# 7duino.net
KiCad netlist of a schematic drawn in EAGLE
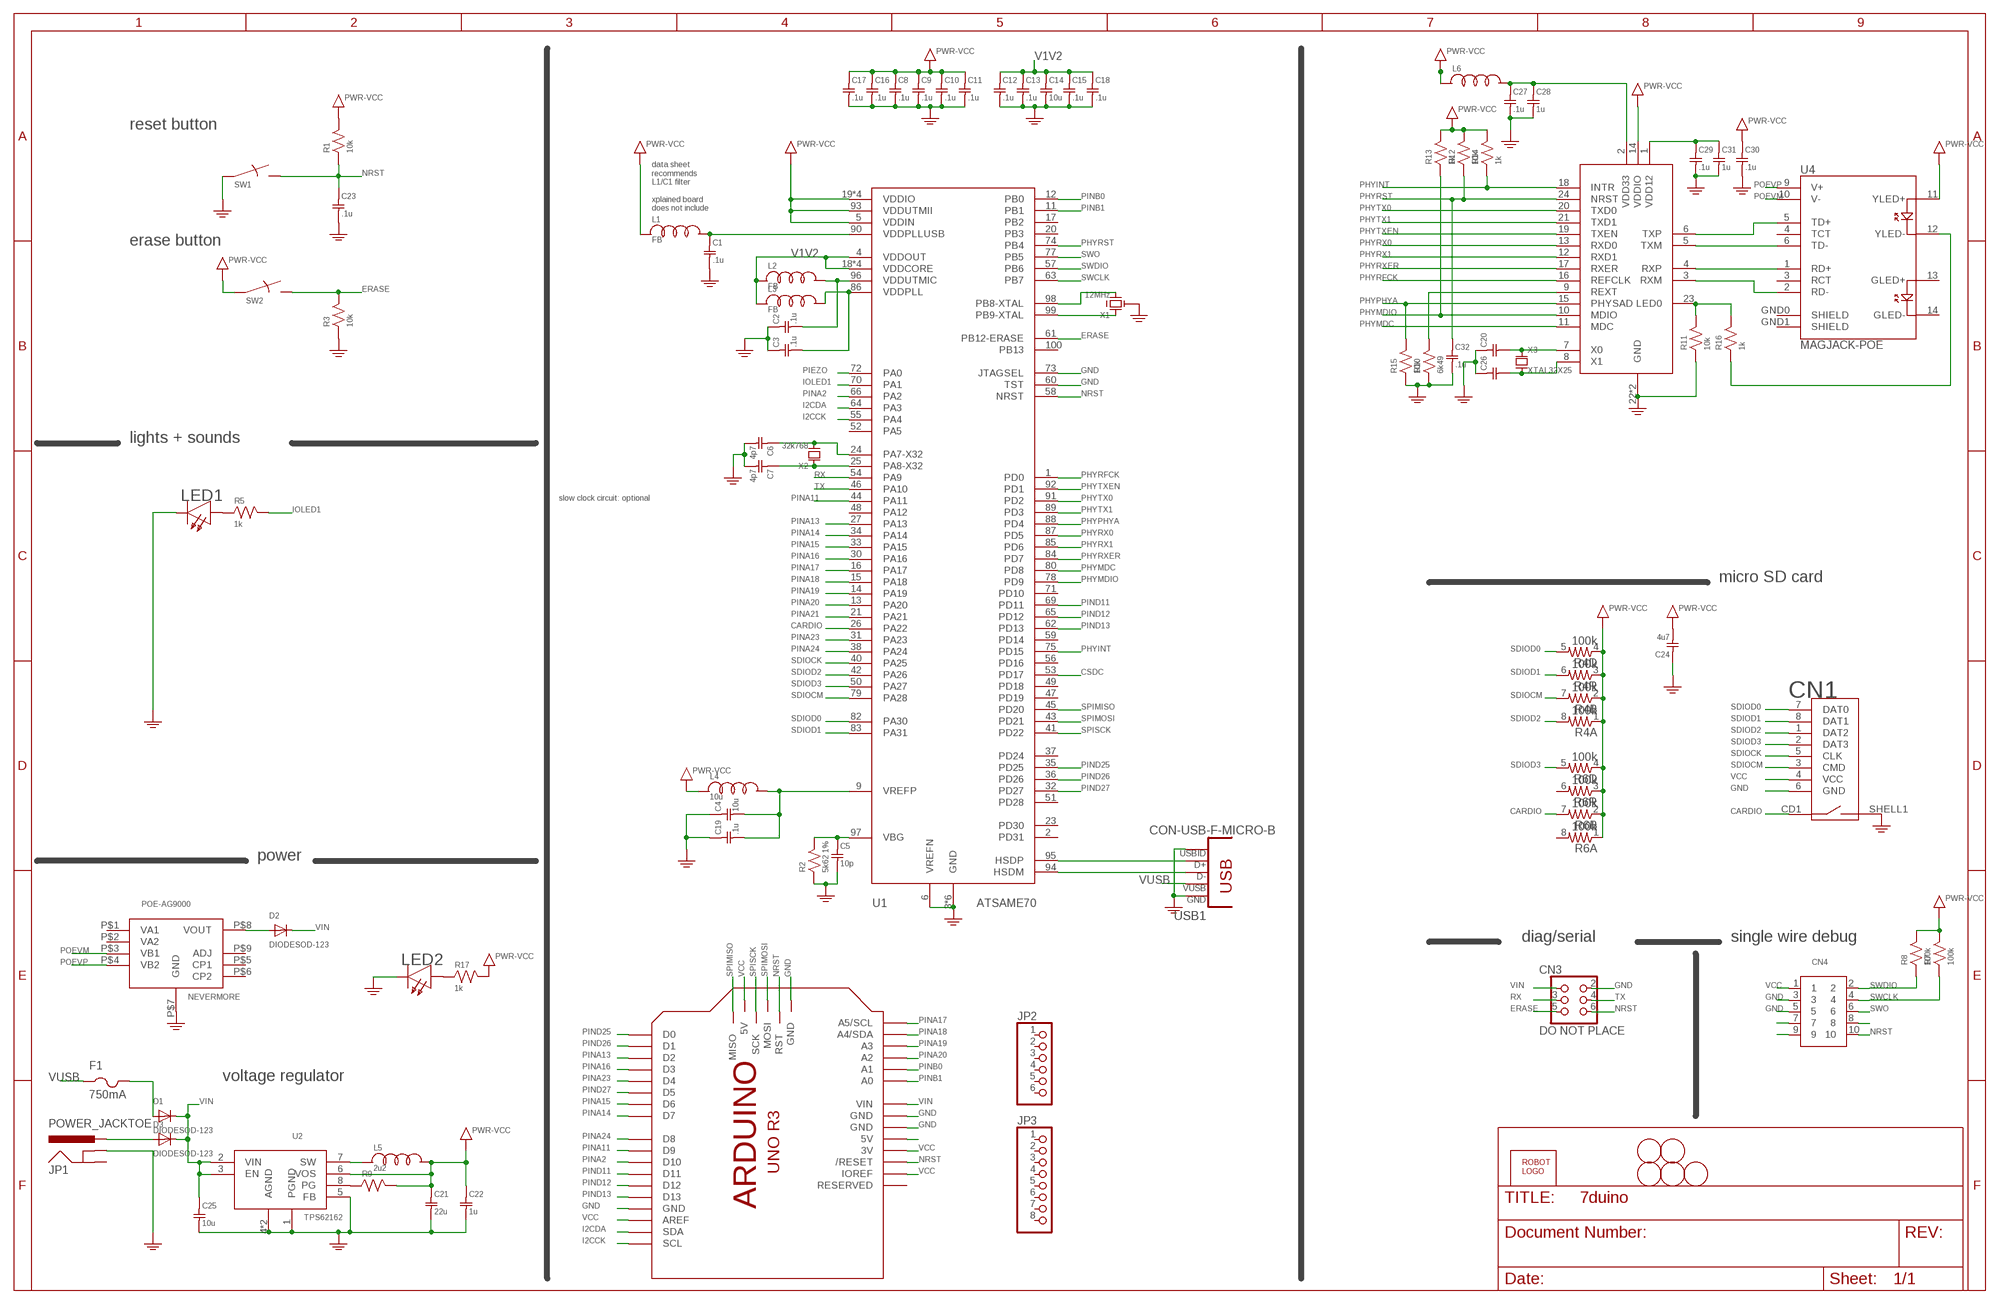
[diagram p0: schematic, sheet 1]

(export (version "E")
  (design (tool "Eeschema 10.0.6"))
  (components
    (comp (ref "C1")
      (value ".1u")
      (footprint "eagle-import:SMD0402")
      (libsource (lib "eagle-import") (part "C-0402"))
    )
    (comp (ref "C2")
      (value ".1u")
      (footprint "eagle-import:SMD0402")
      (libsource (lib "eagle-import") (part "C-0402"))
    )
    (comp (ref "C3")
      (value ".1u")
      (footprint "eagle-import:SMD0402")
      (libsource (lib "eagle-import") (part "C-0402"))
    )
    (comp (ref "C4")
      (value "10u")
      (footprint "eagle-import:SMD0603")
      (libsource (lib "eagle-import") (part "C0603"))
    )
    (comp (ref "C5")
      (value "10p")
      (footprint "eagle-import:SMD0402")
      (libsource (lib "eagle-import") (part "C-0402"))
    )
    (comp (ref "C6")
      (value "4p7")
      (footprint "eagle-import:SMD0402")
      (libsource (lib "eagle-import") (part "C-0402"))
    )
    (comp (ref "C7")
      (value "4p7")
      (footprint "eagle-import:SMD0402")
      (libsource (lib "eagle-import") (part "C-0402"))
    )
    (comp (ref "C8")
      (value ".1u")
      (footprint "eagle-import:SMD0402")
      (libsource (lib "eagle-import") (part "C-0402"))
    )
    (comp (ref "C9")
      (value ".1u")
      (footprint "eagle-import:SMD0402")
      (libsource (lib "eagle-import") (part "C-0402"))
    )
    (comp (ref "C10")
      (value ".1u")
      (footprint "eagle-import:SMD0402")
      (libsource (lib "eagle-import") (part "C-0402"))
    )
    (comp (ref "C11")
      (value ".1u")
      (footprint "eagle-import:SMD0402")
      (libsource (lib "eagle-import") (part "C-0402"))
    )
    (comp (ref "C12")
      (value ".1u")
      (footprint "eagle-import:SMD0402")
      (libsource (lib "eagle-import") (part "C-0402"))
    )
    (comp (ref "C13")
      (value ".1u")
      (footprint "eagle-import:SMD0402")
      (libsource (lib "eagle-import") (part "C-0402"))
    )
    (comp (ref "C14")
      (value "10u")
      (footprint "eagle-import:SMD0603")
      (libsource (lib "eagle-import") (part "C0603"))
    )
    (comp (ref "C15")
      (value ".1u")
      (footprint "eagle-import:SMD0402")
      (libsource (lib "eagle-import") (part "C-0402"))
    )
    (comp (ref "C16")
      (value ".1u")
      (footprint "eagle-import:SMD0402")
      (libsource (lib "eagle-import") (part "C-0402"))
    )
    (comp (ref "C17")
      (value ".1u")
      (footprint "eagle-import:SMD0402")
      (libsource (lib "eagle-import") (part "C-0402"))
    )
    (comp (ref "C18")
      (value ".1u")
      (footprint "eagle-import:SMD0402")
      (libsource (lib "eagle-import") (part "C-0402"))
    )
    (comp (ref "C19")
      (value ".1u")
      (footprint "eagle-import:SMD0402")
      (libsource (lib "eagle-import") (part "C-0402"))
    )
    (comp (ref "C20")
      (value "C-0402")
      (footprint "eagle-import:SMD0402")
      (libsource (lib "eagle-import") (part "C-0402"))
    )
    (comp (ref "C21")
      (value "22u")
      (footprint "eagle-import:SMD0805")
      (libsource (lib "eagle-import") (part "C0805"))
    )
    (comp (ref "C22")
      (value "1u")
      (footprint "eagle-import:SMD0402")
      (libsource (lib "eagle-import") (part "C-0402"))
    )
    (comp (ref "C23")
      (value ".1u")
      (footprint "eagle-import:SMD0402")
      (libsource (lib "eagle-import") (part "C-0402"))
    )
    (comp (ref "C24")
      (value "4u7")
      (footprint "eagle-import:SMD0603")
      (libsource (lib "eagle-import") (part "C0603"))
    )
    (comp (ref "C25")
      (value "10u")
      (footprint "eagle-import:SMD0603")
      (libsource (lib "eagle-import") (part "C0603"))
    )
    (comp (ref "C26")
      (value "C-0402")
      (footprint "eagle-import:SMD0402")
      (libsource (lib "eagle-import") (part "C-0402"))
    )
    (comp (ref "C27")
      (value ".1u")
      (footprint "eagle-import:SMD0402")
      (libsource (lib "eagle-import") (part "C-0402"))
    )
    (comp (ref "C28")
      (value "1u")
      (footprint "eagle-import:SMD0402")
      (libsource (lib "eagle-import") (part "C-0402"))
    )
    (comp (ref "C29")
      (value ".1u")
      (footprint "eagle-import:SMD0402")
      (libsource (lib "eagle-import") (part "C-0402"))
    )
    (comp (ref "C30")
      (value ".1u")
      (footprint "eagle-import:SMD0402")
      (libsource (lib "eagle-import") (part "C-0402"))
    )
    (comp (ref "C31")
      (value "1u")
      (footprint "eagle-import:SMD0402")
      (libsource (lib "eagle-import") (part "C-0402"))
    )
    (comp (ref "C32")
      (value ".1u")
      (footprint "eagle-import:SMD0402")
      (libsource (lib "eagle-import") (part "C-0402"))
    )
    (comp (ref "CN1")
      (value "MICROSD-EJECT")
      (footprint "eagle-import:MICROSD_EJECTOR")
      (libsource (lib "eagle-import") (part "MICROSD-EJECT"))
    )
    (comp (ref "CN3")
      (value "DO NOT PLACE")
      (footprint "eagle-import:HEADER-3X2-POGO")
      (libsource (lib "eagle-import") (part "HEADER-3X2-POGO"))
    )
    (comp (ref "CN4")
      (value "DO NOT PLACE")
      (footprint "eagle-import:M127-5X2-F")
      (libsource (lib "eagle-import") (part "HEADER-5X2-SMD-F"))
    )
    (comp (ref "D1")
      (value "DIODESOD-123")
      (footprint "eagle-import:SOD-123")
      (libsource (lib "eagle-import") (part "DIODESOD-123"))
    )
    (comp (ref "D2")
      (value "DIODESOD-123")
      (footprint "eagle-import:SOD-123")
      (libsource (lib "eagle-import") (part "DIODESOD-123"))
    )
    (comp (ref "D3")
      (value "DIODESOD-123")
      (footprint "eagle-import:SOD-123")
      (libsource (lib "eagle-import") (part "DIODESOD-123"))
    )
    (comp (ref "F1")
      (value "750mA")
      (footprint "eagle-import:SMD1206")
      (libsource (lib "eagle-import") (part "FUSE"))
    )
    (comp (ref "JP1")
      (value "POWER_JACKTOE")
      (footprint "eagle-import:POWER_JACK_SMD_OVERPASTE_TOE")
      (libsource (lib "eagle-import") (part "POWER_JACKTOE"))
    )
    (comp (ref "JP2")
      (value "PINHD-1X6CLEAN")
      (footprint "eagle-import:1X06-CLEAN")
      (libsource (lib "eagle-import") (part "PINHD-1X6CLEAN"))
    )
    (comp (ref "JP3")
      (value "PINHD-1X8CLEANBIG")
      (footprint "eagle-import:1X08-CLEANBIG")
      (libsource (lib "eagle-import") (part "PINHD-1X8CLEANBIG"))
    )
    (comp (ref "L1")
      (value "FB")
      (footprint "eagle-import:SMD0402")
      (libsource (lib "eagle-import") (part "L-0402"))
    )
    (comp (ref "L2")
      (value "FB")
      (footprint "eagle-import:SMD0402")
      (libsource (lib "eagle-import") (part "L-0402"))
    )
    (comp (ref "L3")
      (value "FB")
      (footprint "eagle-import:SMD0402")
      (libsource (lib "eagle-import") (part "L-0402"))
    )
    (comp (ref "L4")
      (value "10u")
      (footprint "eagle-import:SMD0402")
      (libsource (lib "eagle-import") (part "L-0402"))
    )
    (comp (ref "L5")
      (value "2u2")
      (footprint "eagle-import:SMD1210")
      (libsource (lib "eagle-import") (part "L-1210"))
    )
    (comp (ref "L6")
      (value "L-0402")
      (footprint "eagle-import:SMD0402")
      (libsource (lib "eagle-import") (part "L-0402"))
    )
    (comp (ref "LED1")
      (value "white")
      (footprint "eagle-import:SMD0603D")
      (libsource (lib "eagle-import") (part "LED"))
    )
    (comp (ref "LED2")
      (value "white")
      (footprint "eagle-import:SMD0603D")
      (libsource (lib "eagle-import") (part "LED"))
    )
    (comp (ref "M1")
      (value "ARDUINO_R3_ICSP_NODIM")
      (footprint "eagle-import:ARDUINOR3_ICSP_NODIM")
      (libsource (lib "eagle-import") (part "ARDUINO_R3_ICSP_NODIM"))
    )
    (comp (ref "NEVERMORE")
      (value "POE-AG9000")
      (footprint "eagle-import:POE-AG9000")
      (libsource (lib "eagle-import") (part "POE-AG9000"))
    )
    (comp (ref "R1")
      (value "10k")
      (footprint "eagle-import:SMD0402")
      (libsource (lib "eagle-import") (part "R-0402"))
    )
    (comp (ref "R2")
      (value "5k62 1%")
      (footprint "eagle-import:SMD0402")
      (libsource (lib "eagle-import") (part "R-0402"))
    )
    (comp (ref "R3")
      (value "10k")
      (footprint "eagle-import:SMD0402")
      (libsource (lib "eagle-import") (part "R-0402"))
    )
    (comp (ref "R4")
      (value "100k")
      (footprint "eagle-import:SMD-0603-ARV")
      (libsource (lib "eagle-import") (part "R-ARRAY40603-ARV"))
    )
    (comp (ref "R5")
      (value "1k")
      (footprint "eagle-import:SMD0402")
      (libsource (lib "eagle-import") (part "R-0402"))
    )
    (comp (ref "R6")
      (value "100k")
      (footprint "eagle-import:SMD-0603-ARV")
      (libsource (lib "eagle-import") (part "R-ARRAY40603-ARV"))
    )
    (comp (ref "R7")
      (value "100k")
      (footprint "eagle-import:SMD0402")
      (libsource (lib "eagle-import") (part "R-0402"))
    )
    (comp (ref "R8")
      (value "100k")
      (footprint "eagle-import:SMD0402")
      (libsource (lib "eagle-import") (part "R-0402"))
    )
    (comp (ref "R9")
      (value "R-0402")
      (footprint "eagle-import:SMD0402")
      (libsource (lib "eagle-import") (part "R-0402"))
    )
    (comp (ref "R10")
      (value "6k49")
      (footprint "eagle-import:SMD0402")
      (libsource (lib "eagle-import") (part "R-0402"))
    )
    (comp (ref "R11")
      (value "10k")
      (footprint "eagle-import:SMD0402")
      (libsource (lib "eagle-import") (part "R-0402"))
    )
    (comp (ref "R12")
      (value "10k")
      (footprint "eagle-import:SMD0402")
      (libsource (lib "eagle-import") (part "R-0402"))
    )
    (comp (ref "R13")
      (value "1k")
      (footprint "eagle-import:SMD0402")
      (libsource (lib "eagle-import") (part "R-0402"))
    )
    (comp (ref "R14")
      (value "1k")
      (footprint "eagle-import:SMD0402")
      (libsource (lib "eagle-import") (part "R-0402"))
    )
    (comp (ref "R15")
      (value "10k")
      (footprint "eagle-import:SMD0402")
      (libsource (lib "eagle-import") (part "R-0402"))
    )
    (comp (ref "R16")
      (value "1k")
      (footprint "eagle-import:SMD0402")
      (libsource (lib "eagle-import") (part "R-0402"))
    )
    (comp (ref "R17")
      (value "1k")
      (footprint "eagle-import:SMD0402")
      (libsource (lib "eagle-import") (part "R-0402"))
    )
    (comp (ref "SW1")
      (value "SWITCHKMR211")
      (footprint "eagle-import:KMR211")
      (libsource (lib "eagle-import") (part "SWITCHKMR211"))
    )
    (comp (ref "SW2")
      (value "SWITCHKMR211")
      (footprint "eagle-import:KMR211")
      (libsource (lib "eagle-import") (part "SWITCHKMR211"))
    )
    (comp (ref "U$1")
      (value "ROBOTMAN-LOGO2")
      (footprint "eagle-import:ROBOTMAN-LOGO2")
      (libsource (lib "eagle-import") (part "ROBOTMAN-LOGO2"))
    )
    (comp (ref "U$2")
      (value "FIDUCIAL")
      (footprint "eagle-import:FIDUCIAL_1MM")
      (libsource (lib "eagle-import") (part "FIDUCIAL"))
    )
    (comp (ref "U$3")
      (value "FIDUCIAL")
      (footprint "eagle-import:FIDUCIAL_1MM")
      (libsource (lib "eagle-import") (part "FIDUCIAL"))
    )
    (comp (ref "U$4")
      (value "FIDUCIAL")
      (footprint "eagle-import:FIDUCIAL_1MM")
      (libsource (lib "eagle-import") (part "FIDUCIAL"))
    )
    (comp (ref "U$5")
      (value "FIDUCIAL")
      (footprint "eagle-import:FIDUCIAL_1MM")
      (libsource (lib "eagle-import") (part "FIDUCIAL"))
    )
    (comp (ref "U$6")
      (value "FIDUCIAL")
      (footprint "eagle-import:FIDUCIAL_1MM")
      (libsource (lib "eagle-import") (part "FIDUCIAL"))
    )
    (comp (ref "U1")
      (value "ATSAME70")
      (footprint "eagle-import:TQFP-100-14X14MM")
      (libsource (lib "eagle-import") (part "ATSAME70"))
    )
    (comp (ref "U2")
      (value "TPS62162")
      (footprint "eagle-import:WSON8")
      (libsource (lib "eagle-import") (part "TPS62125"))
    )
    (comp (ref "U3")
      (value "KSZ8081RNA")
      (footprint "eagle-import:LGA24EP")
      (libsource (lib "eagle-import") (part "KSZ8081RNA"))
    )
    (comp (ref "U4")
      (value "MAGJACK-POE")
      (footprint "eagle-import:MAGJACK-POE")
      (libsource (lib "eagle-import") (part "MAGJACK-POE"))
    )
    (comp (ref "USB1")
      (value "CON-USB-F-MICRO-B")
      (footprint "eagle-import:CONN_USB_MICRO-B")
      (libsource (lib "eagle-import") (part "CON-USB-F-MICRO-B"))
    )
    (comp (ref "X1")
      (value "12MHz")
      (footprint "eagle-import:RESONATOR-CSTCE")
      (libsource (lib "eagle-import") (part "RESONATORCTCE"))
    )
    (comp (ref "X2")
      (value "32k768")
      (footprint "eagle-import:XTAL-32X15")
      (libsource (lib "eagle-import") (part "XTAL32X15"))
    )
    (comp (ref "X3")
      (value "XTAL32X25")
      (footprint "eagle-import:XTAL-32X25")
      (libsource (lib "eagle-import") (part "XTAL32X25"))
    )
  )
  (nets
    (net (code "1") (name "/CARDIO") (class "Default")
      (node (ref "CN1") (pin "CD1") (pinfunction "SW1_CD1") (pintype "bidirectional"))
      (node (ref "R6") (pin "7") (pinfunction "2_7") (pintype "passive"))
      (node (ref "U1") (pin "26") (pinfunction "PA22_26") (pintype "bidirectional"))
    )
    (net (code "2") (name "/CSDC") (class "Default")
      (node (ref "U1") (pin "53") (pinfunction "PD17_53") (pintype "bidirectional"))
    )
    (net (code "3") (name "/ERASE") (class "Default")
      (node (ref "CN3") (pin "5") (pinfunction "P$5_5") (pintype "passive"))
      (node (ref "R3") (pin "2") (pinfunction "P$2_2") (pintype "passive"))
      (node (ref "SW2") (pin "2") (pinfunction "P$2_2") (pintype "passive"))
      (node (ref "SW2") (pin "4") (pinfunction "P$2_4") (pintype "passive"))
      (node (ref "U1") (pin "61") (pinfunction "PB12-ERASE_61") (pintype "bidirectional"))
    )
    (net (code "4") (name "/I2CCK") (class "Default")
      (node (ref "M1") (pin "SCL") (pinfunction "SCL_SCL") (pintype "bidirectional"))
      (node (ref "U1") (pin "55") (pinfunction "PA4_55") (pintype "bidirectional"))
    )
    (net (code "5") (name "/I2CDA") (class "Default")
      (node (ref "M1") (pin "SDA") (pinfunction "SDA_SDA") (pintype "bidirectional"))
      (node (ref "U1") (pin "64") (pinfunction "PA3_64") (pintype "bidirectional"))
    )
    (net (code "6") (name "/IOLED1") (class "Default")
      (node (ref "R5") (pin "2") (pinfunction "P$2_2") (pintype "passive"))
      (node (ref "U1") (pin "70") (pinfunction "PA1_70") (pintype "bidirectional"))
    )
    (net (code "7") (name "/NRST") (class "Default")
      (node (ref "C23") (pin "1") (pinfunction "P$1_1") (pintype "passive"))
      (node (ref "CN3") (pin "6") (pinfunction "P$6_6") (pintype "passive"))
      (node (ref "CN4") (pin "10") (pinfunction "10_10") (pintype "passive"))
      (node (ref "M1") (pin "RESET") (pinfunction "/RESET_RESET") (pintype "bidirectional"))
      (node (ref "M1") (pin "RESET_ICSP") (pinfunction "RST_RESET_ICSP") (pintype "passive"))
      (node (ref "R1") (pin "1") (pinfunction "P$1_1") (pintype "passive"))
      (node (ref "SW1") (pin "2") (pinfunction "P$2_2") (pintype "passive"))
      (node (ref "SW1") (pin "4") (pinfunction "P$2_4") (pintype "passive"))
      (node (ref "U1") (pin "58") (pinfunction "NRST_58") (pintype "bidirectional"))
    )
    (net (code "8") (name "/PHYINT") (class "Default")
      (node (ref "R14") (pin "1") (pinfunction "P$1_1") (pintype "passive"))
      (node (ref "U1") (pin "75") (pinfunction "PD15_75") (pintype "bidirectional"))
      (node (ref "U3") (pin "18") (pinfunction "INTR_18") (pintype "bidirectional"))
    )
    (net (code "9") (name "/PHYMDC") (class "Default")
      (node (ref "U1") (pin "80") (pinfunction "PD8_80") (pintype "bidirectional"))
      (node (ref "U3") (pin "11") (pinfunction "MDC_11") (pintype "bidirectional"))
    )
    (net (code "10") (name "/PHYMDIO") (class "Default")
      (node (ref "R13") (pin "1") (pinfunction "P$1_1") (pintype "passive"))
      (node (ref "U1") (pin "78") (pinfunction "PD9_78") (pintype "bidirectional"))
      (node (ref "U3") (pin "10") (pinfunction "MDIO_10") (pintype "bidirectional"))
    )
    (net (code "11") (name "/PHYPHYA") (class "Default")
      (node (ref "R15") (pin "2") (pinfunction "P$2_2") (pintype "passive"))
      (node (ref "U1") (pin "88") (pinfunction "PD4_88") (pintype "bidirectional"))
      (node (ref "U3") (pin "15") (pinfunction "PHYSAD_15") (pintype "bidirectional"))
    )
    (net (code "12") (name "/PHYRFCK") (class "Default")
      (node (ref "U1") (pin "1") (pinfunction "PD0_1") (pintype "bidirectional"))
      (node (ref "U3") (pin "16") (pinfunction "REFCLK_16") (pintype "bidirectional"))
    )
    (net (code "13") (name "/PHYRST") (class "Default")
      (node (ref "C32") (pin "1") (pinfunction "P$1_1") (pintype "passive"))
      (node (ref "R12") (pin "1") (pinfunction "P$1_1") (pintype "passive"))
      (node (ref "U1") (pin "74") (pinfunction "PB4_74") (pintype "bidirectional"))
      (node (ref "U3") (pin "24") (pinfunction "NRST_24") (pintype "bidirectional"))
    )
    (net (code "14") (name "/PHYRX0") (class "Default")
      (node (ref "U1") (pin "87") (pinfunction "PD5_87") (pintype "bidirectional"))
      (node (ref "U3") (pin "13") (pinfunction "RXD0_13") (pintype "bidirectional"))
    )
    (net (code "15") (name "/PHYRX1") (class "Default")
      (node (ref "U1") (pin "85") (pinfunction "PD6_85") (pintype "bidirectional"))
      (node (ref "U3") (pin "12") (pinfunction "RXD1_12") (pintype "bidirectional"))
    )
    (net (code "16") (name "/PHYRXER") (class "Default")
      (node (ref "U1") (pin "84") (pinfunction "PD7_84") (pintype "bidirectional"))
      (node (ref "U3") (pin "17") (pinfunction "RXER_17") (pintype "bidirectional"))
    )
    (net (code "17") (name "/PHYTX0") (class "Default")
      (node (ref "U1") (pin "91") (pinfunction "PD2_91") (pintype "bidirectional"))
      (node (ref "U3") (pin "20") (pinfunction "TXD0_20") (pintype "bidirectional"))
    )
    (net (code "18") (name "/PHYTX1") (class "Default")
      (node (ref "U1") (pin "89") (pinfunction "PD3_89") (pintype "bidirectional"))
      (node (ref "U3") (pin "21") (pinfunction "TXD1_21") (pintype "bidirectional"))
    )
    (net (code "19") (name "/PHYTXEN") (class "Default")
      (node (ref "U1") (pin "92") (pinfunction "PD1_92") (pintype "bidirectional"))
      (node (ref "U3") (pin "19") (pinfunction "TXEN_19") (pintype "bidirectional"))
    )
    (net (code "20") (name "/PIEZO") (class "Default")
      (node (ref "U1") (pin "72") (pinfunction "PA0_72") (pintype "bidirectional"))
    )
    (net (code "21") (name "/PINA2") (class "Default")
      (node (ref "M1") (pin "D10") (pinfunction "D10_D10") (pintype "bidirectional"))
      (node (ref "U1") (pin "66") (pinfunction "PA2_66") (pintype "bidirectional"))
    )
    (net (code "22") (name "/PINA11") (class "Default")
      (node (ref "M1") (pin "D9") (pinfunction "D9_D9") (pintype "bidirectional"))
      (node (ref "U1") (pin "44") (pinfunction "PA11_44") (pintype "bidirectional"))
    )
    (net (code "23") (name "/PINA13") (class "Default")
      (node (ref "M1") (pin "D2") (pinfunction "D2_D2") (pintype "bidirectional"))
      (node (ref "U1") (pin "27") (pinfunction "PA13_27") (pintype "bidirectional"))
    )
    (net (code "24") (name "/PINA14") (class "Default")
      (node (ref "M1") (pin "D7") (pinfunction "D7_D7") (pintype "bidirectional"))
      (node (ref "U1") (pin "34") (pinfunction "PA14_34") (pintype "bidirectional"))
    )
    (net (code "25") (name "/PINA15") (class "Default")
      (node (ref "M1") (pin "D6") (pinfunction "D6_D6") (pintype "bidirectional"))
      (node (ref "U1") (pin "33") (pinfunction "PA15_33") (pintype "bidirectional"))
    )
    (net (code "26") (name "/PINA16") (class "Default")
      (node (ref "M1") (pin "D3") (pinfunction "D3_D3") (pintype "bidirectional"))
      (node (ref "U1") (pin "30") (pinfunction "PA16_30") (pintype "bidirectional"))
    )
    (net (code "27") (name "/PINA17") (class "Default")
      (node (ref "M1") (pin "A5") (pinfunction "A5/SCL_A5") (pintype "bidirectional"))
      (node (ref "U1") (pin "16") (pinfunction "PA17_16") (pintype "bidirectional"))
    )
    (net (code "28") (name "/PINA18") (class "Default")
      (node (ref "M1") (pin "A4") (pinfunction "A4/SDA_A4") (pintype "bidirectional"))
      (node (ref "U1") (pin "15") (pinfunction "PA18_15") (pintype "bidirectional"))
    )
    (net (code "29") (name "/PINA19") (class "Default")
      (node (ref "M1") (pin "A3") (pinfunction "A3_A3") (pintype "bidirectional"))
      (node (ref "U1") (pin "14") (pinfunction "PA19_14") (pintype "bidirectional"))
    )
    (net (code "30") (name "/PINA20") (class "Default")
      (node (ref "M1") (pin "A2") (pinfunction "A2_A2") (pintype "bidirectional"))
      (node (ref "U1") (pin "13") (pinfunction "PA20_13") (pintype "bidirectional"))
    )
    (net (code "31") (name "/PINA21") (class "Default")
      (node (ref "U1") (pin "21") (pinfunction "PA21_21") (pintype "bidirectional"))
    )
    (net (code "32") (name "/PINA23") (class "Default")
      (node (ref "M1") (pin "D4") (pinfunction "D4_D4") (pintype "bidirectional"))
      (node (ref "U1") (pin "31") (pinfunction "PA23_31") (pintype "bidirectional"))
    )
    (net (code "33") (name "/PINA24") (class "Default")
      (node (ref "M1") (pin "D8") (pinfunction "D8_D8") (pintype "bidirectional"))
      (node (ref "U1") (pin "38") (pinfunction "PA24_38") (pintype "bidirectional"))
    )
    (net (code "34") (name "/PINB0") (class "Default")
      (node (ref "M1") (pin "A1") (pinfunction "A1_A1") (pintype "bidirectional"))
      (node (ref "U1") (pin "12") (pinfunction "PB0_12") (pintype "bidirectional"))
    )
    (net (code "35") (name "/PINB1") (class "Default")
      (node (ref "M1") (pin "A0") (pinfunction "A0_A0") (pintype "bidirectional"))
      (node (ref "U1") (pin "11") (pinfunction "PB1_11") (pintype "bidirectional"))
    )
    (net (code "36") (name "/PIND11") (class "Default")
      (node (ref "M1") (pin "D11") (pinfunction "D11_D11") (pintype "bidirectional"))
      (node (ref "U1") (pin "69") (pinfunction "PD11_69") (pintype "bidirectional"))
    )
    (net (code "37") (name "/PIND12") (class "Default")
      (node (ref "M1") (pin "D12") (pinfunction "D12_D12") (pintype "bidirectional"))
      (node (ref "U1") (pin "65") (pinfunction "PD12_65") (pintype "bidirectional"))
    )
    (net (code "38") (name "/PIND13") (class "Default")
      (node (ref "M1") (pin "D13") (pinfunction "D13_D13") (pintype "bidirectional"))
      (node (ref "U1") (pin "62") (pinfunction "PD13_62") (pintype "bidirectional"))
    )
    (net (code "39") (name "/PIND25") (class "Default")
      (node (ref "M1") (pin "D0") (pinfunction "D0_D0") (pintype "bidirectional"))
      (node (ref "U1") (pin "35") (pinfunction "PD25_35") (pintype "bidirectional"))
    )
    (net (code "40") (name "/PIND26") (class "Default")
      (node (ref "M1") (pin "D1") (pinfunction "D1_D1") (pintype "bidirectional"))
      (node (ref "U1") (pin "36") (pinfunction "PD26_36") (pintype "bidirectional"))
    )
    (net (code "41") (name "/PIND27") (class "Default")
      (node (ref "M1") (pin "D5") (pinfunction "D5_D5") (pintype "bidirectional"))
      (node (ref "U1") (pin "32") (pinfunction "PD27_32") (pintype "bidirectional"))
    )
    (net (code "42") (name "/POEVM") (class "Default")
      (node (ref "NEVERMORE") (pin "P$3") (pinfunction "VB1_P$3") (pintype "bidirectional"))
      (node (ref "U4") (pin "10") (pinfunction "V-_10") (pintype "bidirectional"))
    )
    (net (code "43") (name "/POEVP") (class "Default")
      (node (ref "NEVERMORE") (pin "P$4") (pinfunction "VB2_P$4") (pintype "bidirectional"))
      (node (ref "U4") (pin "9") (pinfunction "V+_9") (pintype "bidirectional"))
    )
    (net (code "44") (name "/RX") (class "Default")
      (node (ref "CN3") (pin "3") (pinfunction "P$3_3") (pintype "passive"))
      (node (ref "U1") (pin "54") (pinfunction "PA9_54") (pintype "bidirectional"))
    )
    (net (code "45") (name "/SDIOCK") (class "Default")
      (node (ref "CN1") (pin "5") (pinfunction "CLK_5") (pintype "bidirectional"))
      (node (ref "U1") (pin "40") (pinfunction "PA25_40") (pintype "bidirectional"))
    )
    (net (code "46") (name "/SDIOCM") (class "Default")
      (node (ref "CN1") (pin "3") (pinfunction "CMD_3") (pintype "bidirectional"))
      (node (ref "R4") (pin "7") (pinfunction "2_7") (pintype "passive"))
      (node (ref "U1") (pin "79") (pinfunction "PA28_79") (pintype "bidirectional"))
    )
    (net (code "47") (name "/SDIOD0") (class "Default")
      (node (ref "CN1") (pin "7") (pinfunction "DAT0_7") (pintype "bidirectional"))
      (node (ref "R4") (pin "5") (pinfunction "2_5") (pintype "passive"))
      (node (ref "U1") (pin "82") (pinfunction "PA30_82") (pintype "bidirectional"))
    )
    (net (code "48") (name "/SDIOD1") (class "Default")
      (node (ref "CN1") (pin "8") (pinfunction "DAT1_8") (pintype "bidirectional"))
      (node (ref "R4") (pin "6") (pinfunction "2_6") (pintype "passive"))
      (node (ref "U1") (pin "83") (pinfunction "PA31_83") (pintype "bidirectional"))
    )
    (net (code "49") (name "/SDIOD2") (class "Default")
      (node (ref "CN1") (pin "1") (pinfunction "DAT2_1") (pintype "bidirectional"))
      (node (ref "R4") (pin "8") (pinfunction "2_8") (pintype "passive"))
      (node (ref "U1") (pin "42") (pinfunction "PA26_42") (pintype "bidirectional"))
    )
    (net (code "50") (name "/SDIOD3") (class "Default")
      (node (ref "CN1") (pin "2") (pinfunction "DAT3_2") (pintype "bidirectional"))
      (node (ref "R6") (pin "5") (pinfunction "2_5") (pintype "passive"))
      (node (ref "U1") (pin "50") (pinfunction "PA27_50") (pintype "bidirectional"))
    )
    (net (code "51") (name "/SPIMISO") (class "Default")
      (node (ref "M1") (pin "MISO") (pinfunction "MISO_MISO") (pintype "passive"))
      (node (ref "U1") (pin "45") (pinfunction "PD20_45") (pintype "bidirectional"))
    )
    (net (code "52") (name "/SPIMOSI") (class "Default")
      (node (ref "M1") (pin "MOSI") (pinfunction "MOSI_MOSI") (pintype "passive"))
      (node (ref "U1") (pin "43") (pinfunction "PD21_43") (pintype "bidirectional"))
    )
    (net (code "53") (name "/SPISCK") (class "Default")
      (node (ref "M1") (pin "SCK") (pinfunction "SCK_SCK") (pintype "passive"))
      (node (ref "U1") (pin "41") (pinfunction "PD22_41") (pintype "bidirectional"))
    )
    (net (code "54") (name "/SWCLK") (class "Default")
      (node (ref "CN4") (pin "4") (pinfunction "4_4") (pintype "passive"))
      (node (ref "R7") (pin "1") (pinfunction "P$1_1") (pintype "passive"))
      (node (ref "U1") (pin "63") (pinfunction "PB7_63") (pintype "bidirectional"))
    )
    (net (code "55") (name "/SWDIO") (class "Default")
      (node (ref "CN4") (pin "2") (pinfunction "2_2") (pintype "passive"))
      (node (ref "R8") (pin "1") (pinfunction "P$1_1") (pintype "passive"))
      (node (ref "U1") (pin "57") (pinfunction "PB6_57") (pintype "bidirectional"))
    )
    (net (code "56") (name "/SWO") (class "Default")
      (node (ref "CN4") (pin "6") (pinfunction "6_6") (pintype "passive"))
      (node (ref "U1") (pin "77") (pinfunction "PB5_77") (pintype "bidirectional"))
    )
    (net (code "57") (name "/TX") (class "Default")
      (node (ref "CN3") (pin "4") (pinfunction "P$4_4") (pintype "passive"))
      (node (ref "U1") (pin "46") (pinfunction "PA10_46") (pintype "bidirectional"))
    )
    (net (code "58") (name "/V1V2") (class "Default")
      (node (ref "C12") (pin "1") (pinfunction "P$1_1") (pintype "passive"))
      (node (ref "C13") (pin "1") (pinfunction "P$1_1") (pintype "passive"))
      (node (ref "C14") (pin "1") (pinfunction "P$1_1") (pintype "passive"))
      (node (ref "C15") (pin "1") (pinfunction "P$1_1") (pintype "passive"))
      (node (ref "C18") (pin "1") (pinfunction "P$1_1") (pintype "passive"))
      (node (ref "L2") (pin "1") (pinfunction "P$1_1") (pintype "passive"))
      (node (ref "L3") (pin "1") (pinfunction "P$1_1") (pintype "passive"))
      (node (ref "U1") (pin "18") (pinfunction "VDDCORE_18") (pintype "bidirectional"))
      (node (ref "U1") (pin "22") (pinfunction "VDDCORE_22") (pintype "bidirectional"))
      (node (ref "U1") (pin "39") (pinfunction "VDDCORE_39") (pintype "bidirectional"))
      (node (ref "U1") (pin "4") (pinfunction "VDDOUT_4") (pintype "bidirectional"))
      (node (ref "U1") (pin "76") (pinfunction "VDDCORE_76") (pintype "bidirectional"))
    )
    (net (code "59") (name "/VIN") (class "Default")
      (node (ref "C25") (pin "1") (pinfunction "P$1_1") (pintype "passive"))
      (node (ref "CN3") (pin "1") (pinfunction "P$1_1") (pintype "passive"))
      (node (ref "D1") (pin "C") (pinfunction "C_C") (pintype "passive"))
      (node (ref "D2") (pin "C") (pinfunction "C_C") (pintype "passive"))
      (node (ref "D3") (pin "C") (pinfunction "C_C") (pintype "passive"))
      (node (ref "M1") (pin "VIN") (pinfunction "VIN_VIN") (pintype "power_in"))
      (node (ref "U2") (pin "2") (pinfunction "VIN_2") (pintype "bidirectional"))
      (node (ref "U2") (pin "3") (pinfunction "EN_3") (pintype "bidirectional"))
    )
    (net (code "60") (name "/VUSB") (class "Default")
      (node (ref "F1") (pin "1") (pinfunction "1_1") (pintype "passive"))
      (node (ref "USB1") (pin "P1") (pinfunction "VUSB_P1") (pintype "bidirectional"))
    )
    (net (code "61") (name "Net-(C1-P$1)") (class "Default")
      (node (ref "C1") (pin "1") (pinfunction "P$1_1") (pintype "passive"))
      (node (ref "L1") (pin "2") (pinfunction "P$2_2") (pintype "passive"))
      (node (ref "U1") (pin "90") (pinfunction "VDDPLLUSB_90") (pintype "bidirectional"))
    )
    (net (code "62") (name "Net-(C2-P$2)") (class "Default")
      (node (ref "C2") (pin "2") (pinfunction "P$2_2") (pintype "passive"))
      (node (ref "L2") (pin "2") (pinfunction "P$2_2") (pintype "passive"))
      (node (ref "U1") (pin "96") (pinfunction "VDDUTMIC_96") (pintype "bidirectional"))
    )
    (net (code "63") (name "Net-(C3-P$2)") (class "Default")
      (node (ref "C3") (pin "2") (pinfunction "P$2_2") (pintype "passive"))
      (node (ref "L3") (pin "2") (pinfunction "P$2_2") (pintype "passive"))
      (node (ref "U1") (pin "86") (pinfunction "VDDPLL_86") (pintype "bidirectional"))
    )
    (net (code "64") (name "Net-(C5-P$1)") (class "Default")
      (node (ref "C5") (pin "1") (pinfunction "P$1_1") (pintype "passive"))
      (node (ref "R2") (pin "2") (pinfunction "P$2_2") (pintype "passive"))
      (node (ref "U1") (pin "97") (pinfunction "VBG_97") (pintype "bidirectional"))
    )
    (net (code "65") (name "Net-(C6-P$1)") (class "Default")
      (node (ref "C6") (pin "1") (pinfunction "P$1_1") (pintype "passive"))
      (node (ref "U1") (pin "24") (pinfunction "PA7-X32_24") (pintype "bidirectional"))
      (node (ref "X2") (pin "P$2") (pinfunction "P$2_P$2") (pintype "passive"))
    )
    (net (code "66") (name "Net-(C7-P$1)") (class "Default")
      (node (ref "C7") (pin "1") (pinfunction "P$1_1") (pintype "passive"))
      (node (ref "U1") (pin "25") (pinfunction "PA8-X32_25") (pintype "bidirectional"))
      (node (ref "X2") (pin "P$1") (pinfunction "P$1_P$1") (pintype "passive"))
    )
    (net (code "67") (name "Net-(C19-P$2)") (class "Default")
      (node (ref "C19") (pin "2") (pinfunction "P$2_2") (pintype "passive"))
      (node (ref "C4") (pin "2") (pinfunction "P$2_2") (pintype "passive"))
      (node (ref "L4") (pin "2") (pinfunction "P$2_2") (pintype "passive"))
      (node (ref "U1") (pin "9") (pinfunction "VREFP_9") (pintype "bidirectional"))
    )
    (net (code "68") (name "Net-(C20-P$2)") (class "Default")
      (node (ref "C20") (pin "2") (pinfunction "P$2_2") (pintype "passive"))
      (node (ref "U3") (pin "7") (pinfunction "X0_7") (pintype "bidirectional"))
      (node (ref "X3") (pin "1") (pinfunction "P$1_1") (pintype "passive"))
    )
    (net (code "69") (name "Net-(C26-P$2)") (class "Default")
      (node (ref "C26") (pin "2") (pinfunction "P$2_2") (pintype "passive"))
      (node (ref "U3") (pin "8") (pinfunction "X1_8") (pintype "bidirectional"))
      (node (ref "X3") (pin "3") (pinfunction "P$2_3") (pintype "passive"))
    )
    (net (code "70") (name "Net-(C27-P$1)") (class "Default")
      (node (ref "C27") (pin "1") (pinfunction "P$1_1") (pintype "passive"))
      (node (ref "C28") (pin "1") (pinfunction "P$1_1") (pintype "passive"))
      (node (ref "L6") (pin "2") (pinfunction "P$2_2") (pintype "passive"))
      (node (ref "U3") (pin "2") (pinfunction "VDD33_2") (pintype "bidirectional"))
    )
    (net (code "71") (name "Net-(C29-P$1)") (class "Default")
      (node (ref "C29") (pin "1") (pinfunction "P$1_1") (pintype "passive"))
      (node (ref "C31") (pin "1") (pinfunction "P$1_1") (pintype "passive"))
      (node (ref "U3") (pin "1") (pinfunction "VDD12_1") (pintype "bidirectional"))
    )
    (net (code "72") (name "Net-(D1-PadA)") (class "Default")
      (node (ref "D1") (pin "A") (pinfunction "A_A") (pintype "passive"))
      (node (ref "F1") (pin "2") (pinfunction "2_2") (pintype "passive"))
    )
    (net (code "73") (name "Net-(JP1-PWR)") (class "Default")
      (node (ref "D3") (pin "A") (pinfunction "A_A") (pintype "passive"))
      (node (ref "JP1") (pin "VIN0") (pinfunction "PWR_VIN0") (pintype "bidirectional"))
    )
    (net (code "74") (name "Net-(L5-P$1)") (class "Default")
      (node (ref "L5") (pin "1") (pinfunction "P$1_1") (pintype "passive"))
      (node (ref "U2") (pin "7") (pinfunction "SW_7") (pintype "bidirectional"))
    )
    (net (code "75") (name "Net-(NEVERMORE-VOUT)") (class "Default")
      (node (ref "D2") (pin "A") (pinfunction "A_A") (pintype "passive"))
      (node (ref "NEVERMORE") (pin "P$8") (pinfunction "VOUT_P$8") (pintype "bidirectional"))
    )
    (net (code "76") (name "Net-(R5-P$1)") (class "Default")
      (node (ref "LED1") (pin "A") (pinfunction "A_A") (pintype "passive"))
      (node (ref "R5") (pin "1") (pinfunction "P$1_1") (pintype "passive"))
    )
    (net (code "77") (name "Net-(R9-P$1)") (class "Default")
      (node (ref "R9") (pin "1") (pinfunction "P$1_1") (pintype "passive"))
      (node (ref "U2") (pin "8") (pinfunction "PG_8") (pintype "bidirectional"))
    )
    (net (code "78") (name "Net-(R10-P$2)") (class "Default")
      (node (ref "R10") (pin "2") (pinfunction "P$2_2") (pintype "passive"))
      (node (ref "U3") (pin "9") (pinfunction "REXT_9") (pintype "bidirectional"))
    )
    (net (code "79") (name "Net-(R11-P$2)") (class "Default")
      (node (ref "R11") (pin "2") (pinfunction "P$2_2") (pintype "passive"))
      (node (ref "R16") (pin "2") (pinfunction "P$2_2") (pintype "passive"))
      (node (ref "U3") (pin "23") (pinfunction "LED0_23") (pintype "bidirectional"))
    )
    (net (code "80") (name "Net-(R16-P$1)") (class "Default")
      (node (ref "R16") (pin "1") (pinfunction "P$1_1") (pintype "passive"))
      (node (ref "U4") (pin "12") (pinfunction "YLED-_12") (pintype "bidirectional"))
    )
    (net (code "81") (name "Net-(R17-P$1)") (class "Default")
      (node (ref "LED2") (pin "A") (pinfunction "A_A") (pintype "passive"))
      (node (ref "R17") (pin "1") (pinfunction "P$1_1") (pintype "passive"))
    )
    (net (code "82") (name "Net-(U1-HSDM)") (class "Default")
      (node (ref "U1") (pin "94") (pinfunction "HSDM_94") (pintype "bidirectional"))
      (node (ref "USB1") (pin "P2") (pinfunction "D-_P2") (pintype "bidirectional"))
    )
    (net (code "83") (name "Net-(U1-HSDP)") (class "Default")
      (node (ref "U1") (pin "95") (pinfunction "HSDP_95") (pintype "bidirectional"))
      (node (ref "USB1") (pin "P3") (pinfunction "D+_P3") (pintype "bidirectional"))
    )
    (net (code "84") (name "Net-(U1-PB8-XTAL)") (class "Default")
      (node (ref "U1") (pin "98") (pinfunction "PB8-XTAL_98") (pintype "bidirectional"))
      (node (ref "X1") (pin "3") (pinfunction "X2_3") (pintype "passive"))
    )
    (net (code "85") (name "Net-(U1-PB9-XTAL)") (class "Default")
      (node (ref "U1") (pin "99") (pinfunction "PB9-XTAL_99") (pintype "bidirectional"))
      (node (ref "X1") (pin "1") (pinfunction "X1_1") (pintype "passive"))
    )
    (net (code "86") (name "Net-(U3-RXM)") (class "Default")
      (node (ref "U3") (pin "3") (pinfunction "RXM_3") (pintype "bidirectional"))
      (node (ref "U4") (pin "2") (pinfunction "RD-_2") (pintype "bidirectional"))
    )
    (net (code "87") (name "Net-(U3-RXP)") (class "Default")
      (node (ref "U3") (pin "4") (pinfunction "RXP_4") (pintype "bidirectional"))
      (node (ref "U4") (pin "1") (pinfunction "RD+_1") (pintype "bidirectional"))
    )
    (net (code "88") (name "Net-(U3-TXM)") (class "Default")
      (node (ref "U3") (pin "5") (pinfunction "TXM_5") (pintype "bidirectional"))
      (node (ref "U4") (pin "6") (pinfunction "TD-_6") (pintype "bidirectional"))
    )
    (net (code "89") (name "Net-(U3-TXP)") (class "Default")
      (node (ref "U3") (pin "6") (pinfunction "TXP_6") (pintype "bidirectional"))
      (node (ref "U4") (pin "5") (pinfunction "TD+_5") (pintype "bidirectional"))
    )
    (net (code "90") (name "PWR-GND") (class "Default")
      (node (ref "C1") (pin "2") (pinfunction "P$2_2") (pintype "passive"))
      (node (ref "C10") (pin "2") (pinfunction "P$2_2") (pintype "passive"))
      (node (ref "C11") (pin "2") (pinfunction "P$2_2") (pintype "passive"))
      (node (ref "C12") (pin "2") (pinfunction "P$2_2") (pintype "passive"))
      (node (ref "C13") (pin "2") (pinfunction "P$2_2") (pintype "passive"))
      (node (ref "C14") (pin "2") (pinfunction "P$2_2") (pintype "passive"))
      (node (ref "C15") (pin "2") (pinfunction "P$2_2") (pintype "passive"))
      (node (ref "C16") (pin "2") (pinfunction "P$2_2") (pintype "passive"))
      (node (ref "C17") (pin "2") (pinfunction "P$2_2") (pintype "passive"))
      (node (ref "C18") (pin "2") (pinfunction "P$2_2") (pintype "passive"))
      (node (ref "C19") (pin "1") (pinfunction "P$1_1") (pintype "passive"))
      (node (ref "C2") (pin "1") (pinfunction "P$1_1") (pintype "passive"))
      (node (ref "C20") (pin "1") (pinfunction "P$1_1") (pintype "passive"))
      (node (ref "C21") (pin "2") (pinfunction "P$2_2") (pintype "passive"))
      (node (ref "C22") (pin "2") (pinfunction "P$2_2") (pintype "passive"))
      (node (ref "C23") (pin "2") (pinfunction "P$2_2") (pintype "passive"))
      (node (ref "C24") (pin "1") (pinfunction "P$1_1") (pintype "passive"))
      (node (ref "C25") (pin "2") (pinfunction "P$2_2") (pintype "passive"))
      (node (ref "C26") (pin "1") (pinfunction "P$1_1") (pintype "passive"))
      (node (ref "C27") (pin "2") (pinfunction "P$2_2") (pintype "passive"))
      (node (ref "C28") (pin "2") (pinfunction "P$2_2") (pintype "passive"))
      (node (ref "C29") (pin "2") (pinfunction "P$2_2") (pintype "passive"))
      (node (ref "C3") (pin "1") (pinfunction "P$1_1") (pintype "passive"))
      (node (ref "C30") (pin "2") (pinfunction "P$2_2") (pintype "passive"))
      (node (ref "C31") (pin "2") (pinfunction "P$2_2") (pintype "passive"))
      (node (ref "C32") (pin "2") (pinfunction "P$2_2") (pintype "passive"))
      (node (ref "C4") (pin "1") (pinfunction "P$1_1") (pintype "passive"))
      (node (ref "C5") (pin "2") (pinfunction "P$2_2") (pintype "passive"))
      (node (ref "C6") (pin "2") (pinfunction "P$2_2") (pintype "passive"))
      (node (ref "C7") (pin "2") (pinfunction "P$2_2") (pintype "passive"))
      (node (ref "C8") (pin "2") (pinfunction "P$2_2") (pintype "passive"))
      (node (ref "C9") (pin "2") (pinfunction "P$2_2") (pintype "passive"))
      (node (ref "CN1") (pin "6") (pinfunction "GND_6") (pintype "bidirectional"))
      (node (ref "CN1") (pin "SHELL1") (pinfunction "SW2_SHELL1") (pintype "bidirectional"))
      (node (ref "CN3") (pin "2") (pinfunction "P$2_2") (pintype "passive"))
      (node (ref "CN4") (pin "3") (pinfunction "3_3") (pintype "passive"))
      (node (ref "CN4") (pin "5") (pinfunction "5_5") (pintype "passive"))
      (node (ref "JP1") (pin "GND") (pinfunction "GNDBREAK_GND") (pintype "bidirectional"))
      (node (ref "LED1") (pin "C") (pinfunction "C_C") (pintype "passive"))
      (node (ref "LED2") (pin "C") (pinfunction "C_C") (pintype "passive"))
      (node (ref "M1") (pin "GND") (pinfunction "GND_GND") (pintype "power_in"))
      (node (ref "M1") (pin "GND@1") (pinfunction "GND_GND@1") (pintype "power_in"))
      (node (ref "M1") (pin "GND@2") (pinfunction "GND_GND@2") (pintype "passive"))
      (node (ref "M1") (pin "GND@3") (pinfunction "GND_GND@3") (pintype "power_in"))
      (node (ref "NEVERMORE") (pin "P$7") (pinfunction "GND_P$7") (pintype "bidirectional"))
      (node (ref "R10") (pin "1") (pinfunction "P$1_1") (pintype "passive"))
      (node (ref "R11") (pin "1") (pinfunction "P$1_1") (pintype "passive"))
      (node (ref "R15") (pin "1") (pinfunction "P$1_1") (pintype "passive"))
      (node (ref "R2") (pin "1") (pinfunction "P$1_1") (pintype "passive"))
      (node (ref "R3") (pin "1") (pinfunction "P$1_1") (pintype "passive"))
      (node (ref "SW1") (pin "1") (pinfunction "P$1_1") (pintype "passive"))
      (node (ref "SW1") (pin "3") (pinfunction "P$1_3") (pintype "passive"))
      (node (ref "U1") (pin "10") (pinfunction "GND_10") (pintype "bidirectional"))
      (node (ref "U1") (pin "29") (pinfunction "GND_29") (pintype "bidirectional"))
      (node (ref "U1") (pin "3") (pinfunction "GND_3") (pintype "bidirectional"))
      (node (ref "U1") (pin "6") (pinfunction "VREFN_6") (pintype "bidirectional"))
      (node (ref "U1") (pin "60") (pinfunction "TST_60") (pintype "bidirectional"))
      (node (ref "U1") (pin "67") (pinfunction "GND_67") (pintype "bidirectional"))
      (node (ref "U1") (pin "7") (pinfunction "GND_7") (pintype "bidirectional"))
      (node (ref "U1") (pin "73") (pinfunction "JTAGSEL_73") (pintype "bidirectional"))
      (node (ref "U1") (pin "8") (pinfunction "GND_8") (pintype "bidirectional"))
      (node (ref "U2") (pin "1") (pinfunction "PGND_1") (pintype "bidirectional"))
      (node (ref "U2") (pin "4") (pinfunction "AGND_4") (pintype "bidirectional"))
      (node (ref "U2") (pin "5") (pinfunction "FB_5") (pintype "bidirectional"))
      (node (ref "U2") (pin "P$9") (pinfunction "AGND_P$9") (pintype "bidirectional"))
      (node (ref "U3") (pin "22") (pinfunction "GND_22") (pintype "bidirectional"))
      (node (ref "U3") (pin "P$1") (pinfunction "GND_P$1") (pintype "bidirectional"))
      (node (ref "USB1") (pin "P4") (pinfunction "USBID_P4") (pintype "bidirectional"))
      (node (ref "USB1") (pin "P5") (pinfunction "GND_P5") (pintype "bidirectional"))
      (node (ref "X1") (pin "2") (pinfunction "G_2") (pintype "input"))
    )
    (net (code "91") (name "PWR-VCC") (class "Default")
      (node (ref "C10") (pin "1") (pinfunction "P$1_1") (pintype "passive"))
      (node (ref "C11") (pin "1") (pinfunction "P$1_1") (pintype "passive"))
      (node (ref "C16") (pin "1") (pinfunction "P$1_1") (pintype "passive"))
      (node (ref "C17") (pin "1") (pinfunction "P$1_1") (pintype "passive"))
      (node (ref "C21") (pin "1") (pinfunction "P$1_1") (pintype "passive"))
      (node (ref "C22") (pin "1") (pinfunction "P$1_1") (pintype "passive"))
      (node (ref "C24") (pin "2") (pinfunction "P$2_2") (pintype "passive"))
      (node (ref "C30") (pin "1") (pinfunction "P$1_1") (pintype "passive"))
      (node (ref "C8") (pin "1") (pinfunction "P$1_1") (pintype "passive"))
      (node (ref "C9") (pin "1") (pinfunction "P$1_1") (pintype "passive"))
      (node (ref "CN1") (pin "4") (pinfunction "VCC_4") (pintype "bidirectional"))
      (node (ref "CN4") (pin "1") (pinfunction "1_1") (pintype "passive"))
      (node (ref "L1") (pin "1") (pinfunction "P$1_1") (pintype "passive"))
      (node (ref "L4") (pin "1") (pinfunction "P$1_1") (pintype "passive"))
      (node (ref "L5") (pin "2") (pinfunction "P$2_2") (pintype "passive"))
      (node (ref "L6") (pin "1") (pinfunction "P$1_1") (pintype "passive"))
      (node (ref "M1") (pin "3V") (pinfunction "3V_3V") (pintype "power_in"))
      (node (ref "M1") (pin "5V_ICSP") (pinfunction "5V_5V_ICSP") (pintype "passive"))
      (node (ref "M1") (pin "AREF") (pinfunction "AREF_AREF") (pintype "bidirectional"))
      (node (ref "M1") (pin "IOREF") (pinfunction "IOREF_IOREF") (pintype "output"))
      (node (ref "R1") (pin "2") (pinfunction "P$2_2") (pintype "passive"))
      (node (ref "R12") (pin "2") (pinfunction "P$2_2") (pintype "passive"))
      (node (ref "R13") (pin "2") (pinfunction "P$2_2") (pintype "passive"))
      (node (ref "R14") (pin "2") (pinfunction "P$2_2") (pintype "passive"))
      (node (ref "R17") (pin "2") (pinfunction "P$2_2") (pintype "passive"))
      (node (ref "R4") (pin "1") (pinfunction "1_1") (pintype "passive"))
      (node (ref "R4") (pin "2") (pinfunction "1_2") (pintype "passive"))
      (node (ref "R4") (pin "3") (pinfunction "1_3") (pintype "passive"))
      (node (ref "R4") (pin "4") (pinfunction "1_4") (pintype "passive"))
      (node (ref "R6") (pin "1") (pinfunction "1_1") (pintype "passive"))
      (node (ref "R6") (pin "2") (pinfunction "1_2") (pintype "passive"))
      (node (ref "R6") (pin "3") (pinfunction "1_3") (pintype "passive"))
      (node (ref "R6") (pin "4") (pinfunction "1_4") (pintype "passive"))
      (node (ref "R7") (pin "2") (pinfunction "P$2_2") (pintype "passive"))
      (node (ref "R8") (pin "2") (pinfunction "P$2_2") (pintype "passive"))
      (node (ref "R9") (pin "2") (pinfunction "P$2_2") (pintype "passive"))
      (node (ref "SW2") (pin "1") (pinfunction "P$1_1") (pintype "passive"))
      (node (ref "SW2") (pin "3") (pinfunction "P$1_3") (pintype "passive"))
      (node (ref "U1") (pin "19") (pinfunction "VDDIO_19") (pintype "bidirectional"))
      (node (ref "U1") (pin "28") (pinfunction "VDDIO_28") (pintype "bidirectional"))
      (node (ref "U1") (pin "5") (pinfunction "VDDIN_5") (pintype "bidirectional"))
      (node (ref "U1") (pin "68") (pinfunction "VDDIO_68") (pintype "bidirectional"))
      (node (ref "U1") (pin "81") (pinfunction "VDDIO_81") (pintype "bidirectional"))
      (node (ref "U1") (pin "93") (pinfunction "VDDUTMII_93") (pintype "bidirectional"))
      (node (ref "U2") (pin "6") (pinfunction "VOS_6") (pintype "bidirectional"))
      (node (ref "U3") (pin "14") (pinfunction "VDDIO_14") (pintype "bidirectional"))
      (node (ref "U4") (pin "11") (pinfunction "YLED+_11") (pintype "bidirectional"))
    )
    (net (code "92") (name "unconnected-(CN4-Pad7)") (class "Default")
      (node (ref "CN4") (pin "7") (pinfunction "7_7") (pintype "passive"))
    )
    (net (code "93") (name "unconnected-(CN4-Pad8)") (class "Default")
      (node (ref "CN4") (pin "8") (pinfunction "8_8") (pintype "passive"))
    )
    (net (code "94") (name "unconnected-(CN4-Pad9)") (class "Default")
      (node (ref "CN4") (pin "9") (pinfunction "9_9") (pintype "passive"))
    )
    (net (code "95") (name "unconnected-(JP1-GND-PadP$4)") (class "Default")
      (node (ref "JP1") (pin "P$4") (pinfunction "GND_P$4") (pintype "bidirectional"))
    )
    (net (code "96") (name "unconnected-(JP2-Pad1)") (class "Default")
      (node (ref "JP2") (pin "1") (pinfunction "1_1") (pintype "passive"))
    )
    (net (code "97") (name "unconnected-(JP2-Pad2)") (class "Default")
      (node (ref "JP2") (pin "2") (pinfunction "2_2") (pintype "passive"))
    )
    (net (code "98") (name "unconnected-(JP2-Pad3)") (class "Default")
      (node (ref "JP2") (pin "3") (pinfunction "3_3") (pintype "passive"))
    )
    (net (code "99") (name "unconnected-(JP2-Pad4)") (class "Default")
      (node (ref "JP2") (pin "4") (pinfunction "4_4") (pintype "passive"))
    )
    (net (code "100") (name "unconnected-(JP2-Pad5)") (class "Default")
      (node (ref "JP2") (pin "5") (pinfunction "5_5") (pintype "passive"))
    )
    (net (code "101") (name "unconnected-(JP2-Pad6)") (class "Default")
      (node (ref "JP2") (pin "6") (pinfunction "6_6") (pintype "passive"))
    )
    (net (code "102") (name "unconnected-(JP3-Pad1)") (class "Default")
      (node (ref "JP3") (pin "1") (pinfunction "1_1") (pintype "passive"))
    )
    (net (code "103") (name "unconnected-(JP3-Pad2)") (class "Default")
      (node (ref "JP3") (pin "2") (pinfunction "2_2") (pintype "passive"))
    )
    (net (code "104") (name "unconnected-(JP3-Pad3)") (class "Default")
      (node (ref "JP3") (pin "3") (pinfunction "3_3") (pintype "passive"))
    )
    (net (code "105") (name "unconnected-(JP3-Pad4)") (class "Default")
      (node (ref "JP3") (pin "4") (pinfunction "4_4") (pintype "passive"))
    )
    (net (code "106") (name "unconnected-(JP3-Pad5)") (class "Default")
      (node (ref "JP3") (pin "5") (pinfunction "5_5") (pintype "passive"))
    )
    (net (code "107") (name "unconnected-(JP3-Pad6)") (class "Default")
      (node (ref "JP3") (pin "6") (pinfunction "6_6") (pintype "passive"))
    )
    (net (code "108") (name "unconnected-(JP3-Pad7)") (class "Default")
      (node (ref "JP3") (pin "7") (pinfunction "7_7") (pintype "passive"))
    )
    (net (code "109") (name "unconnected-(JP3-Pad8)") (class "Default")
      (node (ref "JP3") (pin "8") (pinfunction "8_8") (pintype "passive"))
    )
    (net (code "110") (name "unconnected-(M1-Pad5V)") (class "Default")
      (node (ref "M1") (pin "5V") (pinfunction "5V_5V") (pintype "power_in"))
    )
    (net (code "111") (name "unconnected-(M1-PadRESERVED)") (class "Default")
      (node (ref "M1") (pin "RESERVED") (pinfunction "RESERVED_RESERVED") (pintype "no_connect"))
    )
    (net (code "112") (name "unconnected-(NEVERMORE-ADJ-PadP$9)") (class "Default")
      (node (ref "NEVERMORE") (pin "P$9") (pinfunction "ADJ_P$9") (pintype "bidirectional"))
    )
    (net (code "113") (name "unconnected-(NEVERMORE-CP1-PadP$5)") (class "Default")
      (node (ref "NEVERMORE") (pin "P$5") (pinfunction "CP1_P$5") (pintype "bidirectional"))
    )
    (net (code "114") (name "unconnected-(NEVERMORE-CP2-PadP$6)") (class "Default")
      (node (ref "NEVERMORE") (pin "P$6") (pinfunction "CP2_P$6") (pintype "bidirectional"))
    )
    (net (code "115") (name "unconnected-(NEVERMORE-VA1-PadP$1)") (class "Default")
      (node (ref "NEVERMORE") (pin "P$1") (pinfunction "VA1_P$1") (pintype "bidirectional"))
    )
    (net (code "116") (name "unconnected-(NEVERMORE-VA2-PadP$2)") (class "Default")
      (node (ref "NEVERMORE") (pin "P$2") (pinfunction "VA2_P$2") (pintype "bidirectional"))
    )
    (net (code "117") (name "unconnected-(R6A-2-Pad8)") (class "Default")
      (node (ref "R6") (pin "8") (pinfunction "2_8") (pintype "passive"))
    )
    (net (code "118") (name "unconnected-(R6D-2-Pad6)") (class "Default")
      (node (ref "R6") (pin "6") (pinfunction "2_6") (pintype "passive"))
    )
    (net (code "119") (name "unconnected-(U1-PA5-Pad52)") (class "Default")
      (node (ref "U1") (pin "52") (pinfunction "PA5_52") (pintype "bidirectional"))
    )
    (net (code "120") (name "unconnected-(U1-PA12-Pad48)") (class "Default")
      (node (ref "U1") (pin "48") (pinfunction "PA12_48") (pintype "bidirectional"))
    )
    (net (code "121") (name "unconnected-(U1-PB2-Pad17)") (class "Default")
      (node (ref "U1") (pin "17") (pinfunction "PB2_17") (pintype "bidirectional"))
    )
    (net (code "122") (name "unconnected-(U1-PB3-Pad20)") (class "Default")
      (node (ref "U1") (pin "20") (pinfunction "PB3_20") (pintype "bidirectional"))
    )
    (net (code "123") (name "unconnected-(U1-PB13-Pad100)") (class "Default")
      (node (ref "U1") (pin "100") (pinfunction "PB13_100") (pintype "bidirectional"))
    )
    (net (code "124") (name "unconnected-(U1-PD10-Pad71)") (class "Default")
      (node (ref "U1") (pin "71") (pinfunction "PD10_71") (pintype "bidirectional"))
    )
    (net (code "125") (name "unconnected-(U1-PD14-Pad59)") (class "Default")
      (node (ref "U1") (pin "59") (pinfunction "PD14_59") (pintype "bidirectional"))
    )
    (net (code "126") (name "unconnected-(U1-PD16-Pad56)") (class "Default")
      (node (ref "U1") (pin "56") (pinfunction "PD16_56") (pintype "bidirectional"))
    )
    (net (code "127") (name "unconnected-(U1-PD18-Pad49)") (class "Default")
      (node (ref "U1") (pin "49") (pinfunction "PD18_49") (pintype "bidirectional"))
    )
    (net (code "128") (name "unconnected-(U1-PD19-Pad47)") (class "Default")
      (node (ref "U1") (pin "47") (pinfunction "PD19_47") (pintype "bidirectional"))
    )
    (net (code "129") (name "unconnected-(U1-PD24-Pad37)") (class "Default")
      (node (ref "U1") (pin "37") (pinfunction "PD24_37") (pintype "bidirectional"))
    )
    (net (code "130") (name "unconnected-(U1-PD28-Pad51)") (class "Default")
      (node (ref "U1") (pin "51") (pinfunction "PD28_51") (pintype "bidirectional"))
    )
    (net (code "131") (name "unconnected-(U1-PD30-Pad23)") (class "Default")
      (node (ref "U1") (pin "23") (pinfunction "PD30_23") (pintype "bidirectional"))
    )
    (net (code "132") (name "unconnected-(U1-PD31-Pad2)") (class "Default")
      (node (ref "U1") (pin "2") (pinfunction "PD31_2") (pintype "bidirectional"))
    )
    (net (code "133") (name "unconnected-(U4-GLED+-Pad13)") (class "Default")
      (node (ref "U4") (pin "13") (pinfunction "GLED+_13") (pintype "bidirectional"))
    )
    (net (code "134") (name "unconnected-(U4-GLED--Pad14)") (class "Default")
      (node (ref "U4") (pin "14") (pinfunction "GLED-_14") (pintype "bidirectional"))
    )
    (net (code "135") (name "unconnected-(U4-RCT-Pad3)") (class "Default")
      (node (ref "U4") (pin "3") (pinfunction "RCT_3") (pintype "bidirectional"))
    )
    (net (code "136") (name "unconnected-(U4-SHIELD-PadGND0)") (class "Default")
      (node (ref "U4") (pin "GND0") (pinfunction "SHIELD_GND0") (pintype "bidirectional"))
    )
    (net (code "137") (name "unconnected-(U4-SHIELD-PadGND1)") (class "Default")
      (node (ref "U4") (pin "GND1") (pinfunction "SHIELD_GND1") (pintype "bidirectional"))
    )
    (net (code "138") (name "unconnected-(U4-TCT-Pad4)") (class "Default")
      (node (ref "U4") (pin "4") (pinfunction "TCT_4") (pintype "bidirectional"))
    )
  )
)
